# atarimovie.net
KiCad netlist of a schematic drawn in EAGLE
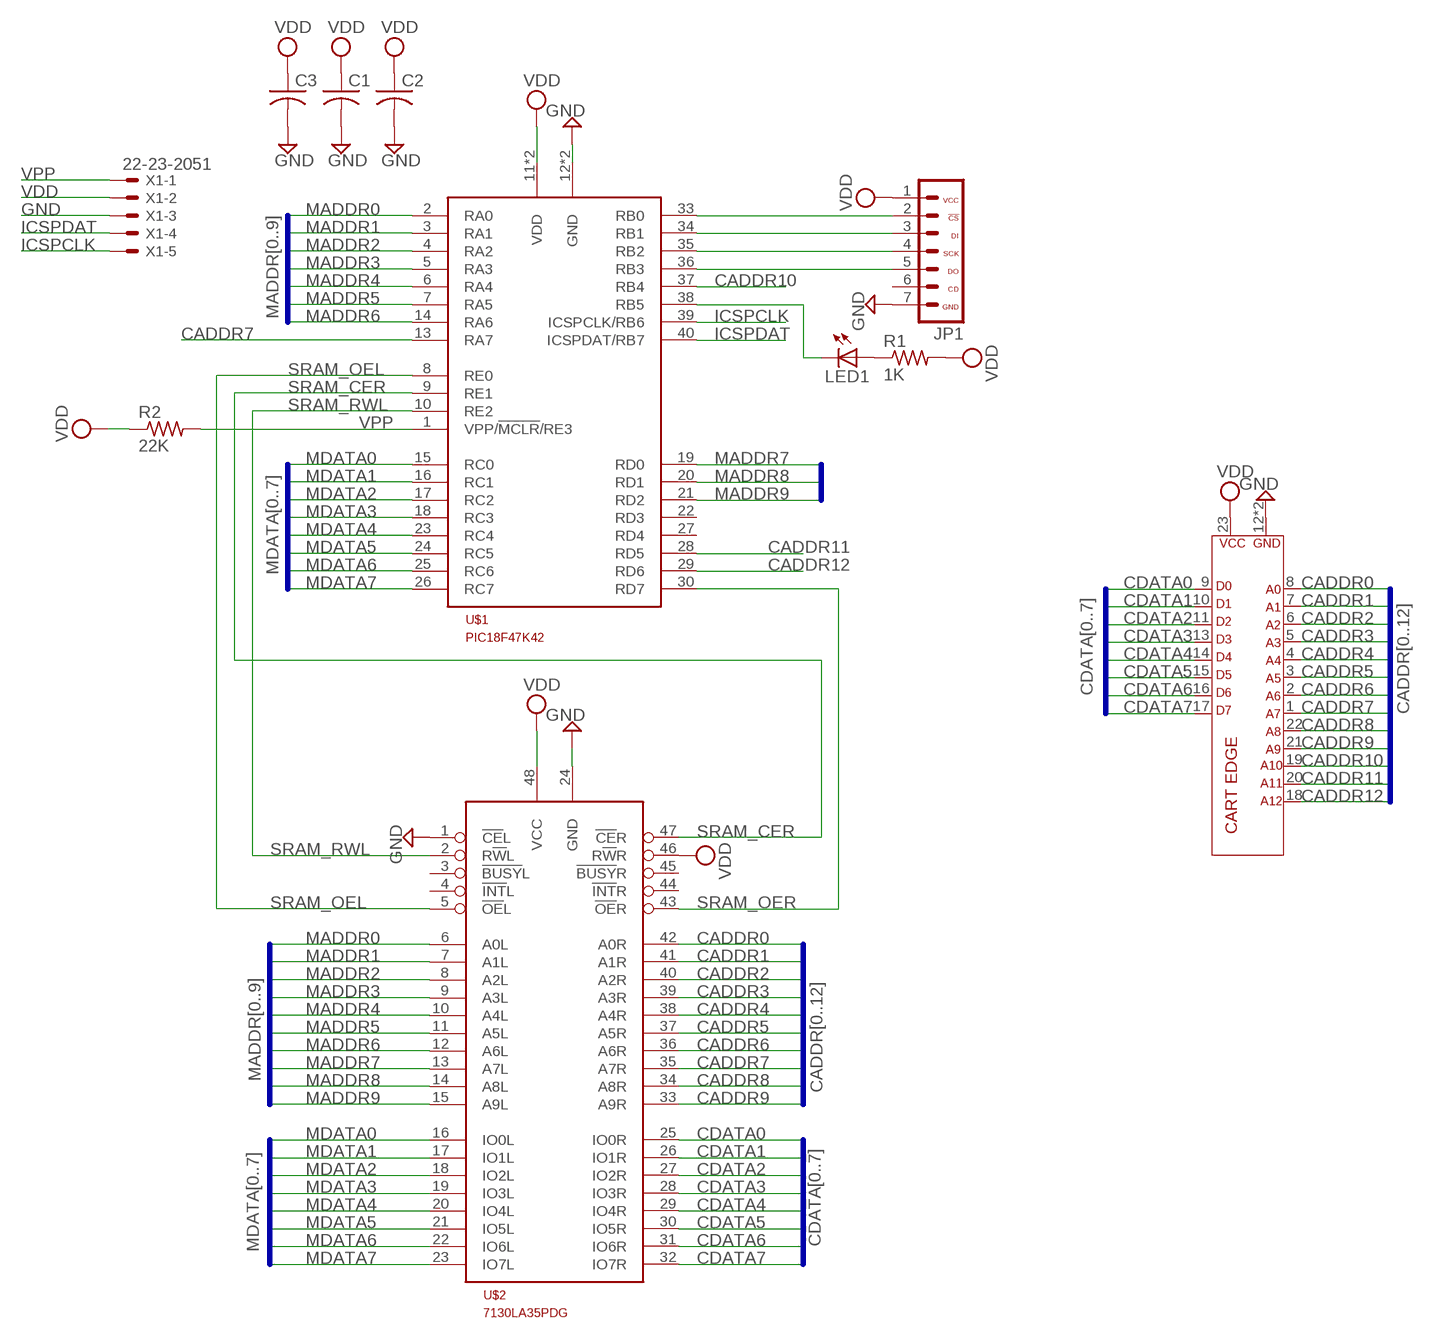
[diagram p0: schematic, sheet 1]

(export (version "E")
  (design (tool "Eeschema 10.0.6"))
  (components
    (comp (ref "C1")
      (value "C-US050-025X075")
      (footprint "eagle-import:C050-025X075")
      (libsource (lib "eagle-import") (part "C-US050-025X075"))
    )
    (comp (ref "C2")
      (value "C-US050-025X075")
      (footprint "eagle-import:C050-025X075")
      (libsource (lib "eagle-import") (part "C-US050-025X075"))
    )
    (comp (ref "C3")
      (value "C-US050-025X075")
      (footprint "eagle-import:C050-025X075")
      (libsource (lib "eagle-import") (part "C-US050-025X075"))
    )
    (comp (ref "J1")
      (value "ATARI-2600MED_NOHOLE")
      (footprint "eagle-import:MED_NOHOLE")
      (libsource (lib "eagle-import") (part "ATARI-2600MED_NOHOLE"))
    )
    (comp (ref "JP1")
      (value "USD_SHIFTER")
      (footprint "eagle-import:USD_SHIFTER")
      (libsource (lib "eagle-import") (part "USD_SHIFTER"))
    )
    (comp (ref "LED1")
      (value "LED3MM")
      (footprint "eagle-import:LED3MM")
      (libsource (lib "eagle-import") (part "LED3MM"))
    )
    (comp (ref "R1")
      (value "1K")
      (footprint "eagle-import:0204_7")
      (libsource (lib "eagle-import") (part "R-US_0204/7"))
    )
    (comp (ref "R2")
      (value "22K")
      (footprint "eagle-import:0204_7")
      (libsource (lib "eagle-import") (part "R-US_0204/7"))
    )
    (comp (ref "U$1")
      (value "PIC18F47K42")
      (footprint "eagle-import:DIP40")
      (libsource (lib "eagle-import") (part "PIC18F47K42"))
    )
    (comp (ref "U$2")
      (value "7130LA35PDG")
      (footprint "eagle-import:DIP48")
      (libsource (lib "eagle-import") (part "7130LA35PDG"))
    )
    (comp (ref "X1")
      (value "22-23-2051")
      (footprint "eagle-import:22-23-2051")
      (fields (field (name "MF") "MOLEX"))
      (libsource (lib "eagle-import") (part "22-23-2051"))
    )
  )
  (nets
    (net (code "5") (name "CADDR0") (class "Default")
      (node (ref "J1") (pin "8") (pinfunction "A0_8") (pintype "bidirectional"))
      (node (ref "U$2") (pin "42") (pinfunction "A0R_42") (pintype "input"))
    )
    (net (code "6") (name "CADDR1") (class "Default")
      (node (ref "J1") (pin "7") (pinfunction "A1_7") (pintype "bidirectional"))
      (node (ref "U$2") (pin "41") (pinfunction "A1R_41") (pintype "input"))
    )
    (net (code "7") (name "CADDR2") (class "Default")
      (node (ref "J1") (pin "6") (pinfunction "A2_6") (pintype "bidirectional"))
      (node (ref "U$2") (pin "40") (pinfunction "A2R_40") (pintype "input"))
    )
    (net (code "8") (name "CADDR3") (class "Default")
      (node (ref "J1") (pin "5") (pinfunction "A3_5") (pintype "bidirectional"))
      (node (ref "U$2") (pin "39") (pinfunction "A3R_39") (pintype "input"))
    )
    (net (code "9") (name "CADDR4") (class "Default")
      (node (ref "J1") (pin "4") (pinfunction "A4_4") (pintype "bidirectional"))
      (node (ref "U$2") (pin "38") (pinfunction "A4R_38") (pintype "input"))
    )
    (net (code "10") (name "CADDR5") (class "Default")
      (node (ref "J1") (pin "3") (pinfunction "A5_3") (pintype "bidirectional"))
      (node (ref "U$2") (pin "37") (pinfunction "A5R_37") (pintype "input"))
    )
    (net (code "11") (name "CADDR6") (class "Default")
      (node (ref "J1") (pin "2") (pinfunction "A6_2") (pintype "bidirectional"))
      (node (ref "U$2") (pin "36") (pinfunction "A6R_36") (pintype "input"))
    )
    (net (code "12") (name "CADDR7") (class "Default")
      (node (ref "J1") (pin "1") (pinfunction "A7_1") (pintype "bidirectional"))
      (node (ref "U$1") (pin "13") (pinfunction "RA7_13") (pintype "bidirectional"))
      (node (ref "U$2") (pin "35") (pinfunction "A7R_35") (pintype "input"))
    )
    (net (code "13") (name "CADDR8") (class "Default")
      (node (ref "J1") (pin "22") (pinfunction "A8_22") (pintype "bidirectional"))
      (node (ref "U$2") (pin "34") (pinfunction "A8R_34") (pintype "input"))
    )
    (net (code "14") (name "CADDR9") (class "Default")
      (node (ref "J1") (pin "21") (pinfunction "A9_21") (pintype "bidirectional"))
      (node (ref "U$2") (pin "33") (pinfunction "A9R_33") (pintype "input"))
    )
    (net (code "15") (name "CADDR10") (class "Default")
      (node (ref "J1") (pin "19") (pinfunction "A10_19") (pintype "bidirectional"))
      (node (ref "U$1") (pin "37") (pinfunction "RB4_37") (pintype "bidirectional"))
    )
    (net (code "16") (name "CADDR11") (class "Default")
      (node (ref "J1") (pin "20") (pinfunction "A11_20") (pintype "bidirectional"))
      (node (ref "U$1") (pin "28") (pinfunction "RD5_28") (pintype "bidirectional"))
    )
    (net (code "17") (name "CADDR12") (class "Default")
      (node (ref "J1") (pin "18") (pinfunction "A12_18") (pintype "bidirectional"))
      (node (ref "U$1") (pin "29") (pinfunction "RD6_29") (pintype "bidirectional"))
    )
    (net (code "18") (name "CDATA0") (class "Default")
      (node (ref "J1") (pin "9") (pinfunction "D0_9") (pintype "bidirectional"))
      (node (ref "U$2") (pin "25") (pinfunction "IO0R_25") (pintype "bidirectional"))
    )
    (net (code "19") (name "CDATA1") (class "Default")
      (node (ref "J1") (pin "10") (pinfunction "D1_10") (pintype "bidirectional"))
      (node (ref "U$2") (pin "26") (pinfunction "IO1R_26") (pintype "bidirectional"))
    )
    (net (code "20") (name "CDATA2") (class "Default")
      (node (ref "J1") (pin "11") (pinfunction "D2_11") (pintype "bidirectional"))
      (node (ref "U$2") (pin "27") (pinfunction "IO2R_27") (pintype "bidirectional"))
    )
    (net (code "21") (name "CDATA3") (class "Default")
      (node (ref "J1") (pin "13") (pinfunction "D3_13") (pintype "bidirectional"))
      (node (ref "U$2") (pin "28") (pinfunction "IO3R_28") (pintype "bidirectional"))
    )
    (net (code "22") (name "CDATA4") (class "Default")
      (node (ref "J1") (pin "14") (pinfunction "D4_14") (pintype "bidirectional"))
      (node (ref "U$2") (pin "29") (pinfunction "IO4R_29") (pintype "bidirectional"))
    )
    (net (code "23") (name "CDATA5") (class "Default")
      (node (ref "J1") (pin "15") (pinfunction "D5_15") (pintype "bidirectional"))
      (node (ref "U$2") (pin "30") (pinfunction "IO5R_30") (pintype "bidirectional"))
    )
    (net (code "24") (name "CDATA6") (class "Default")
      (node (ref "J1") (pin "16") (pinfunction "D6_16") (pintype "bidirectional"))
      (node (ref "U$2") (pin "31") (pinfunction "IO6R_31") (pintype "bidirectional"))
    )
    (net (code "25") (name "CDATA7") (class "Default")
      (node (ref "J1") (pin "17") (pinfunction "D7_17") (pintype "bidirectional"))
      (node (ref "U$2") (pin "32") (pinfunction "IO7R_32") (pintype "bidirectional"))
    )
    (net (code "26") (name "GND") (class "Default")
      (node (ref "C1") (pin "2") (pinfunction "2_2") (pintype "passive"))
      (node (ref "C2") (pin "2") (pinfunction "2_2") (pintype "passive"))
      (node (ref "C3") (pin "2") (pinfunction "2_2") (pintype "passive"))
      (node (ref "J1") (pin "12") (pinfunction "GND_12") (pintype "power_in"))
      (node (ref "J1") (pin "24") (pinfunction "GND_24") (pintype "power_in"))
      (node (ref "JP1") (pin "7") (pinfunction "GND_7") (pintype "power_in"))
      (node (ref "U$1") (pin "12") (pinfunction "GND_12") (pintype "power_in"))
      (node (ref "U$1") (pin "31") (pinfunction "GND_31") (pintype "power_in"))
      (node (ref "U$2") (pin "1") (pinfunction "~{CE}L_1") (pintype "input"))
      (node (ref "U$2") (pin "24") (pinfunction "GND_24") (pintype "power_in"))
      (node (ref "X1") (pin "3") (pinfunction "S_3") (pintype "passive"))
    )
    (net (code "27") (name "ICSPCLK") (class "Default")
      (node (ref "U$1") (pin "39") (pinfunction "ICSPCLK/RB6_39") (pintype "bidirectional"))
      (node (ref "X1") (pin "5") (pinfunction "S_5") (pintype "passive"))
    )
    (net (code "28") (name "ICSPDAT") (class "Default")
      (node (ref "U$1") (pin "40") (pinfunction "ICSPDAT/RB7_40") (pintype "bidirectional"))
      (node (ref "X1") (pin "4") (pinfunction "S_4") (pintype "passive"))
    )
    (net (code "29") (name "MADDR0") (class "Default")
      (node (ref "U$1") (pin "2") (pinfunction "RA0_2") (pintype "bidirectional"))
      (node (ref "U$2") (pin "6") (pinfunction "A0L_6") (pintype "input"))
    )
    (net (code "30") (name "MADDR1") (class "Default")
      (node (ref "U$1") (pin "3") (pinfunction "RA1_3") (pintype "bidirectional"))
      (node (ref "U$2") (pin "7") (pinfunction "A1L_7") (pintype "input"))
    )
    (net (code "31") (name "MADDR2") (class "Default")
      (node (ref "U$1") (pin "4") (pinfunction "RA2_4") (pintype "bidirectional"))
      (node (ref "U$2") (pin "8") (pinfunction "A2L_8") (pintype "input"))
    )
    (net (code "32") (name "MADDR3") (class "Default")
      (node (ref "U$1") (pin "5") (pinfunction "RA3_5") (pintype "bidirectional"))
      (node (ref "U$2") (pin "9") (pinfunction "A3L_9") (pintype "input"))
    )
    (net (code "33") (name "MADDR4") (class "Default")
      (node (ref "U$1") (pin "6") (pinfunction "RA4_6") (pintype "bidirectional"))
      (node (ref "U$2") (pin "10") (pinfunction "A4L_10") (pintype "input"))
    )
    (net (code "34") (name "MADDR5") (class "Default")
      (node (ref "U$1") (pin "7") (pinfunction "RA5_7") (pintype "bidirectional"))
      (node (ref "U$2") (pin "11") (pinfunction "A5L_11") (pintype "input"))
    )
    (net (code "35") (name "MADDR6") (class "Default")
      (node (ref "U$1") (pin "14") (pinfunction "RA6_14") (pintype "bidirectional"))
      (node (ref "U$2") (pin "12") (pinfunction "A6L_12") (pintype "input"))
    )
    (net (code "36") (name "MADDR7") (class "Default")
      (node (ref "U$1") (pin "19") (pinfunction "RD0_19") (pintype "bidirectional"))
      (node (ref "U$2") (pin "13") (pinfunction "A7L_13") (pintype "input"))
    )
    (net (code "37") (name "MADDR8") (class "Default")
      (node (ref "U$1") (pin "20") (pinfunction "RD1_20") (pintype "bidirectional"))
      (node (ref "U$2") (pin "14") (pinfunction "A8L_14") (pintype "input"))
    )
    (net (code "38") (name "MADDR9") (class "Default")
      (node (ref "U$1") (pin "21") (pinfunction "RD2_21") (pintype "bidirectional"))
      (node (ref "U$2") (pin "15") (pinfunction "A9L_15") (pintype "input"))
    )
    (net (code "39") (name "MDATA0") (class "Default")
      (node (ref "U$1") (pin "15") (pinfunction "RC0_15") (pintype "bidirectional"))
      (node (ref "U$2") (pin "16") (pinfunction "IO0L_16") (pintype "bidirectional"))
    )
    (net (code "40") (name "MDATA1") (class "Default")
      (node (ref "U$1") (pin "16") (pinfunction "RC1_16") (pintype "bidirectional"))
      (node (ref "U$2") (pin "17") (pinfunction "IO1L_17") (pintype "bidirectional"))
    )
    (net (code "41") (name "MDATA2") (class "Default")
      (node (ref "U$1") (pin "17") (pinfunction "RC2_17") (pintype "bidirectional"))
      (node (ref "U$2") (pin "18") (pinfunction "IO2L_18") (pintype "bidirectional"))
    )
    (net (code "42") (name "MDATA3") (class "Default")
      (node (ref "U$1") (pin "18") (pinfunction "RC3_18") (pintype "bidirectional"))
      (node (ref "U$2") (pin "19") (pinfunction "IO3L_19") (pintype "bidirectional"))
    )
    (net (code "43") (name "MDATA4") (class "Default")
      (node (ref "U$1") (pin "23") (pinfunction "RC4_23") (pintype "bidirectional"))
      (node (ref "U$2") (pin "20") (pinfunction "IO4L_20") (pintype "bidirectional"))
    )
    (net (code "44") (name "MDATA5") (class "Default")
      (node (ref "U$1") (pin "24") (pinfunction "RC5_24") (pintype "bidirectional"))
      (node (ref "U$2") (pin "21") (pinfunction "IO5L_21") (pintype "bidirectional"))
    )
    (net (code "45") (name "MDATA6") (class "Default")
      (node (ref "U$1") (pin "25") (pinfunction "RC6_25") (pintype "bidirectional"))
      (node (ref "U$2") (pin "22") (pinfunction "IO6L_22") (pintype "bidirectional"))
    )
    (net (code "46") (name "MDATA7") (class "Default")
      (node (ref "U$1") (pin "26") (pinfunction "RC7_26") (pintype "bidirectional"))
      (node (ref "U$2") (pin "23") (pinfunction "IO7L_23") (pintype "bidirectional"))
    )
    (net (code "47") (name "Net-(JP1-DI)") (class "Default")
      (node (ref "JP1") (pin "3") (pinfunction "DI_3") (pintype "output"))
      (node (ref "U$1") (pin "34") (pinfunction "RB1_34") (pintype "bidirectional"))
    )
    (net (code "48") (name "Net-(JP1-DO)") (class "Default")
      (node (ref "JP1") (pin "5") (pinfunction "DO_5") (pintype "input"))
      (node (ref "U$1") (pin "36") (pinfunction "RB3_36") (pintype "bidirectional"))
    )
    (net (code "49") (name "Net-(JP1-SCK)") (class "Default")
      (node (ref "JP1") (pin "4") (pinfunction "SCK_4") (pintype "input"))
      (node (ref "U$1") (pin "35") (pinfunction "RB2_35") (pintype "bidirectional"))
    )
    (net (code "50") (name "Net-(JP1-~{CS})") (class "Default")
      (node (ref "JP1") (pin "2") (pinfunction "~{CS}_2") (pintype "input"))
      (node (ref "U$1") (pin "33") (pinfunction "RB0_33") (pintype "bidirectional"))
    )
    (net (code "51") (name "Net-(LED1-C)") (class "Default")
      (node (ref "LED1") (pin "K") (pinfunction "C_K") (pintype "passive"))
      (node (ref "U$1") (pin "38") (pinfunction "RB5_38") (pintype "bidirectional"))
    )
    (net (code "52") (name "Net-(LED1-PadA)") (class "Default")
      (node (ref "LED1") (pin "A") (pinfunction "A_A") (pintype "passive"))
      (node (ref "R1") (pin "1") (pinfunction "1_1") (pintype "passive"))
    )
    (net (code "53") (name "SRAM_CER") (class "Default")
      (node (ref "U$1") (pin "9") (pinfunction "RE1_9") (pintype "bidirectional"))
      (node (ref "U$2") (pin "47") (pinfunction "~{CE}R_47") (pintype "input"))
    )
    (net (code "54") (name "SRAM_OEL") (class "Default")
      (node (ref "U$1") (pin "8") (pinfunction "RE0_8") (pintype "bidirectional"))
      (node (ref "U$2") (pin "5") (pinfunction "~{OE}L_5") (pintype "input"))
    )
    (net (code "55") (name "SRAM_OER") (class "Default")
      (node (ref "U$1") (pin "30") (pinfunction "RD7_30") (pintype "bidirectional"))
      (node (ref "U$2") (pin "43") (pinfunction "~{OE}R_43") (pintype "input"))
    )
    (net (code "56") (name "SRAM_RWL") (class "Default")
      (node (ref "U$1") (pin "10") (pinfunction "RE2_10") (pintype "bidirectional"))
      (node (ref "U$2") (pin "2") (pinfunction "R~{W}L_2") (pintype "input"))
    )
    (net (code "57") (name "VDD") (class "Default")
      (node (ref "C1") (pin "1") (pinfunction "1_1") (pintype "passive"))
      (node (ref "C2") (pin "1") (pinfunction "1_1") (pintype "passive"))
      (node (ref "C3") (pin "1") (pinfunction "1_1") (pintype "passive"))
      (node (ref "J1") (pin "23") (pinfunction "VCC_23") (pintype "power_in"))
      (node (ref "JP1") (pin "1") (pinfunction "VCC_1") (pintype "power_in"))
      (node (ref "R1") (pin "2") (pinfunction "2_2") (pintype "passive"))
      (node (ref "R2") (pin "1") (pinfunction "1_1") (pintype "passive"))
      (node (ref "U$1") (pin "11") (pinfunction "VDD_11") (pintype "power_in"))
      (node (ref "U$1") (pin "32") (pinfunction "VDD_32") (pintype "power_in"))
      (node (ref "U$2") (pin "46") (pinfunction "R~{W}R_46") (pintype "input"))
      (node (ref "U$2") (pin "48") (pinfunction "VCC_48") (pintype "power_in"))
      (node (ref "X1") (pin "2") (pinfunction "S_2") (pintype "passive"))
    )
    (net (code "58") (name "VPP") (class "Default")
      (node (ref "R2") (pin "2") (pinfunction "2_2") (pintype "passive"))
      (node (ref "U$1") (pin "1") (pinfunction "VPP/~{MCLR}/RE3_1") (pintype "input"))
      (node (ref "X1") (pin "1") (pinfunction "S_1") (pintype "passive"))
    )
    (net (code "59") (name "unconnected-(JP1-CD-Pad6)") (class "Default")
      (node (ref "JP1") (pin "6") (pinfunction "CD_6") (pintype "output"))
    )
    (net (code "60") (name "unconnected-(U$1-RD3-Pad22)") (class "Default")
      (node (ref "U$1") (pin "22") (pinfunction "RD3_22") (pintype "bidirectional"))
    )
    (net (code "61") (name "unconnected-(U$1-RD4-Pad27)") (class "Default")
      (node (ref "U$1") (pin "27") (pinfunction "RD4_27") (pintype "bidirectional"))
    )
    (net (code "62") (name "unconnected-(U$2-~{BUSY}L-Pad3)") (class "Default")
      (node (ref "U$2") (pin "3") (pinfunction "~{BUSY}L_3") (pintype "output"))
    )
    (net (code "63") (name "unconnected-(U$2-~{BUSY}R-Pad45)") (class "Default")
      (node (ref "U$2") (pin "45") (pinfunction "~{BUSY}R_45") (pintype "output"))
    )
    (net (code "64") (name "unconnected-(U$2-~{INT}L-Pad4)") (class "Default")
      (node (ref "U$2") (pin "4") (pinfunction "~{INT}L_4") (pintype "output"))
    )
    (net (code "65") (name "unconnected-(U$2-~{INT}R-Pad44)") (class "Default")
      (node (ref "U$2") (pin "44") (pinfunction "~{INT}R_44") (pintype "output"))
    )
  )
)
